# espnative-deadrail-2-c.net
KiCad netlist of a schematic drawn in EAGLE
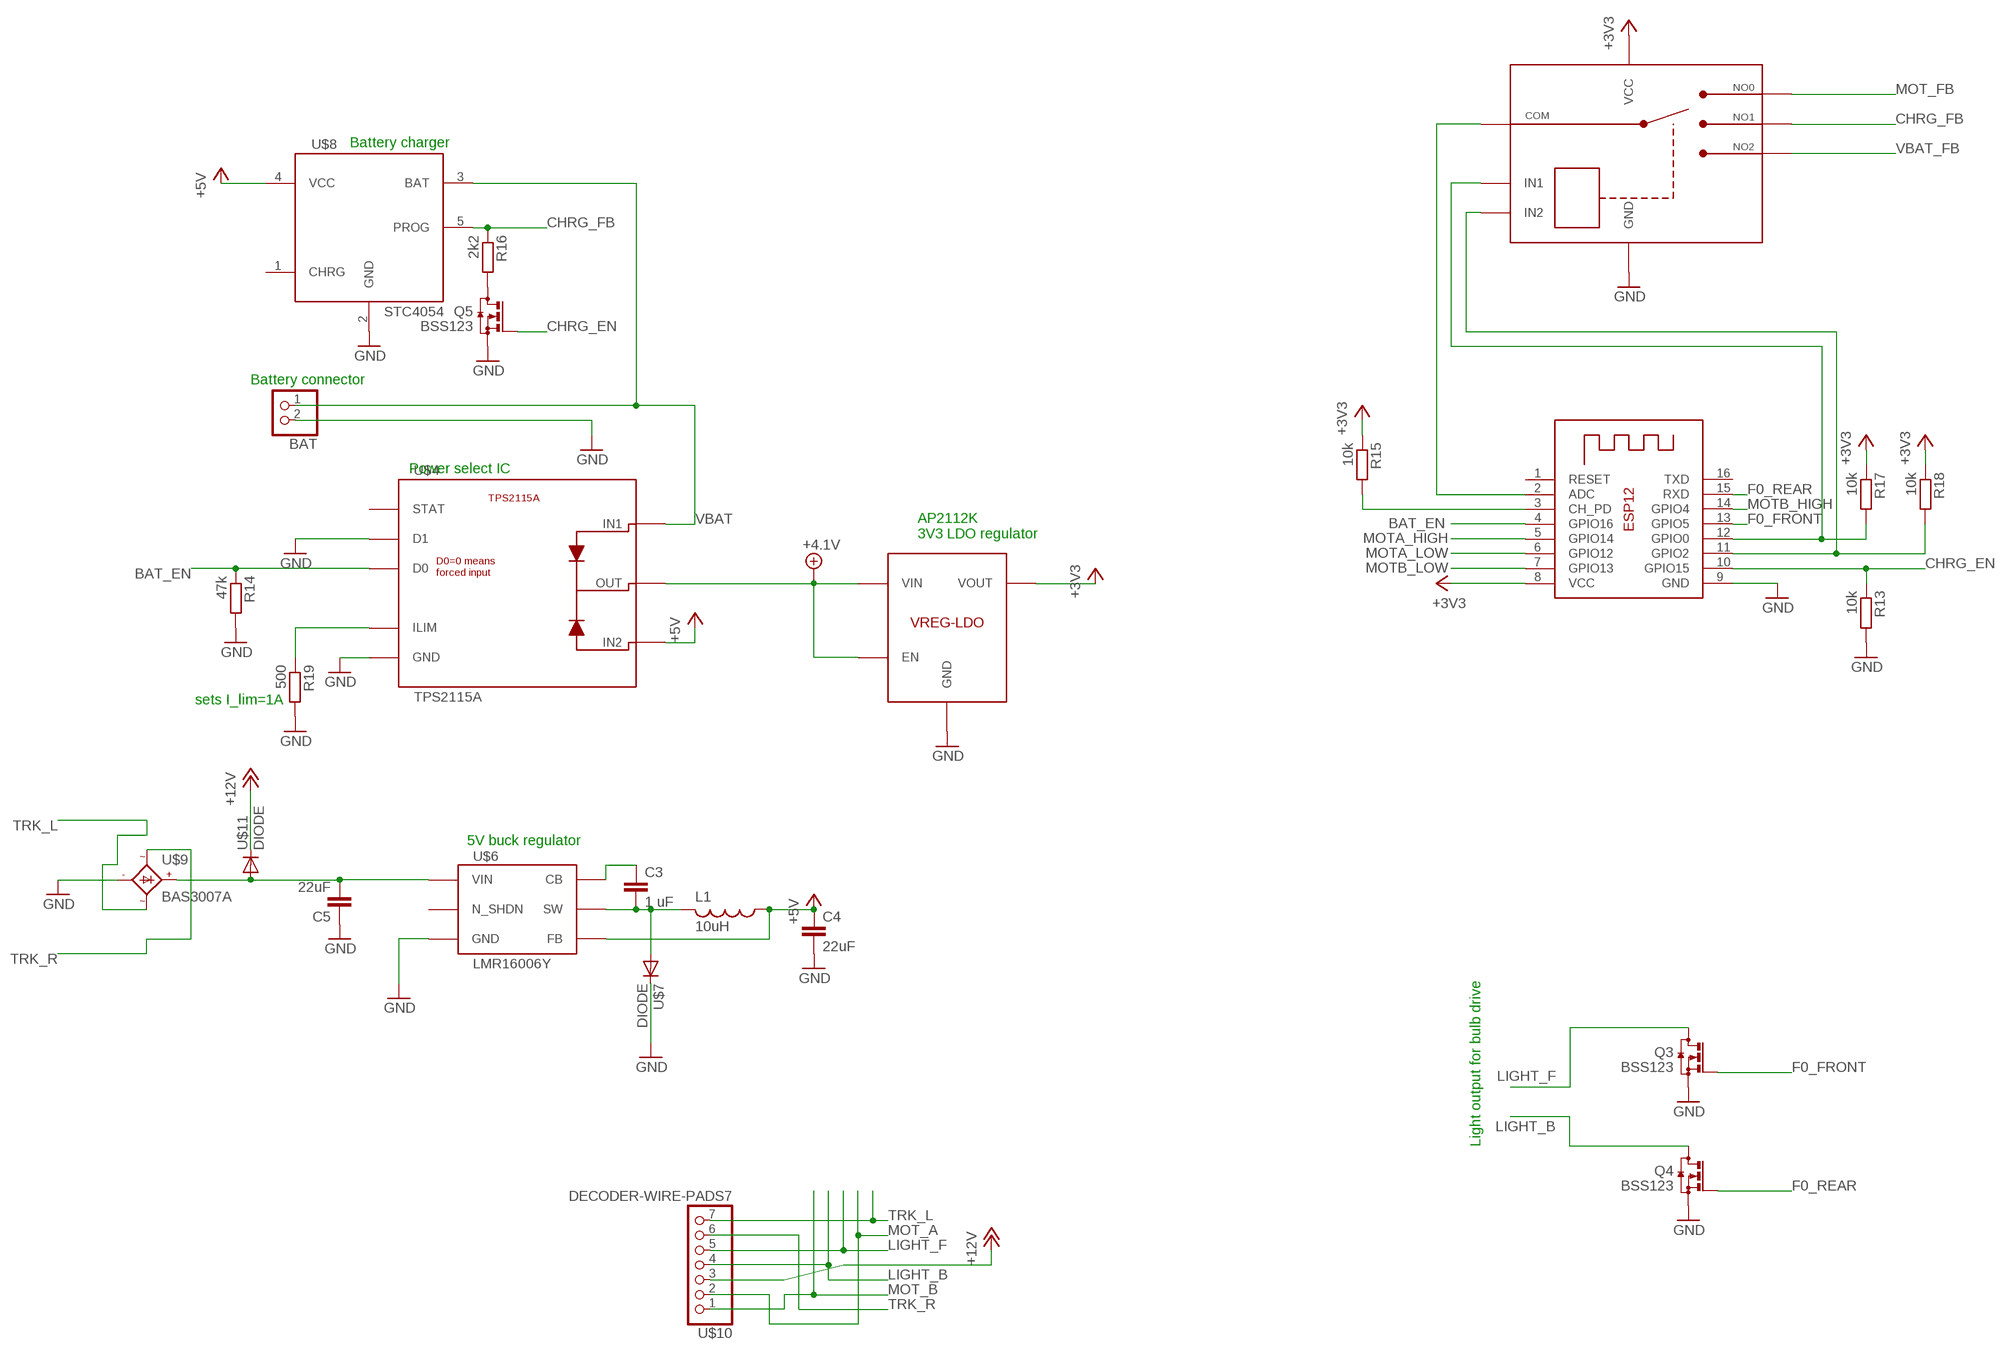
[diagram p0: schematic, sheet 1, part 1 of 2]
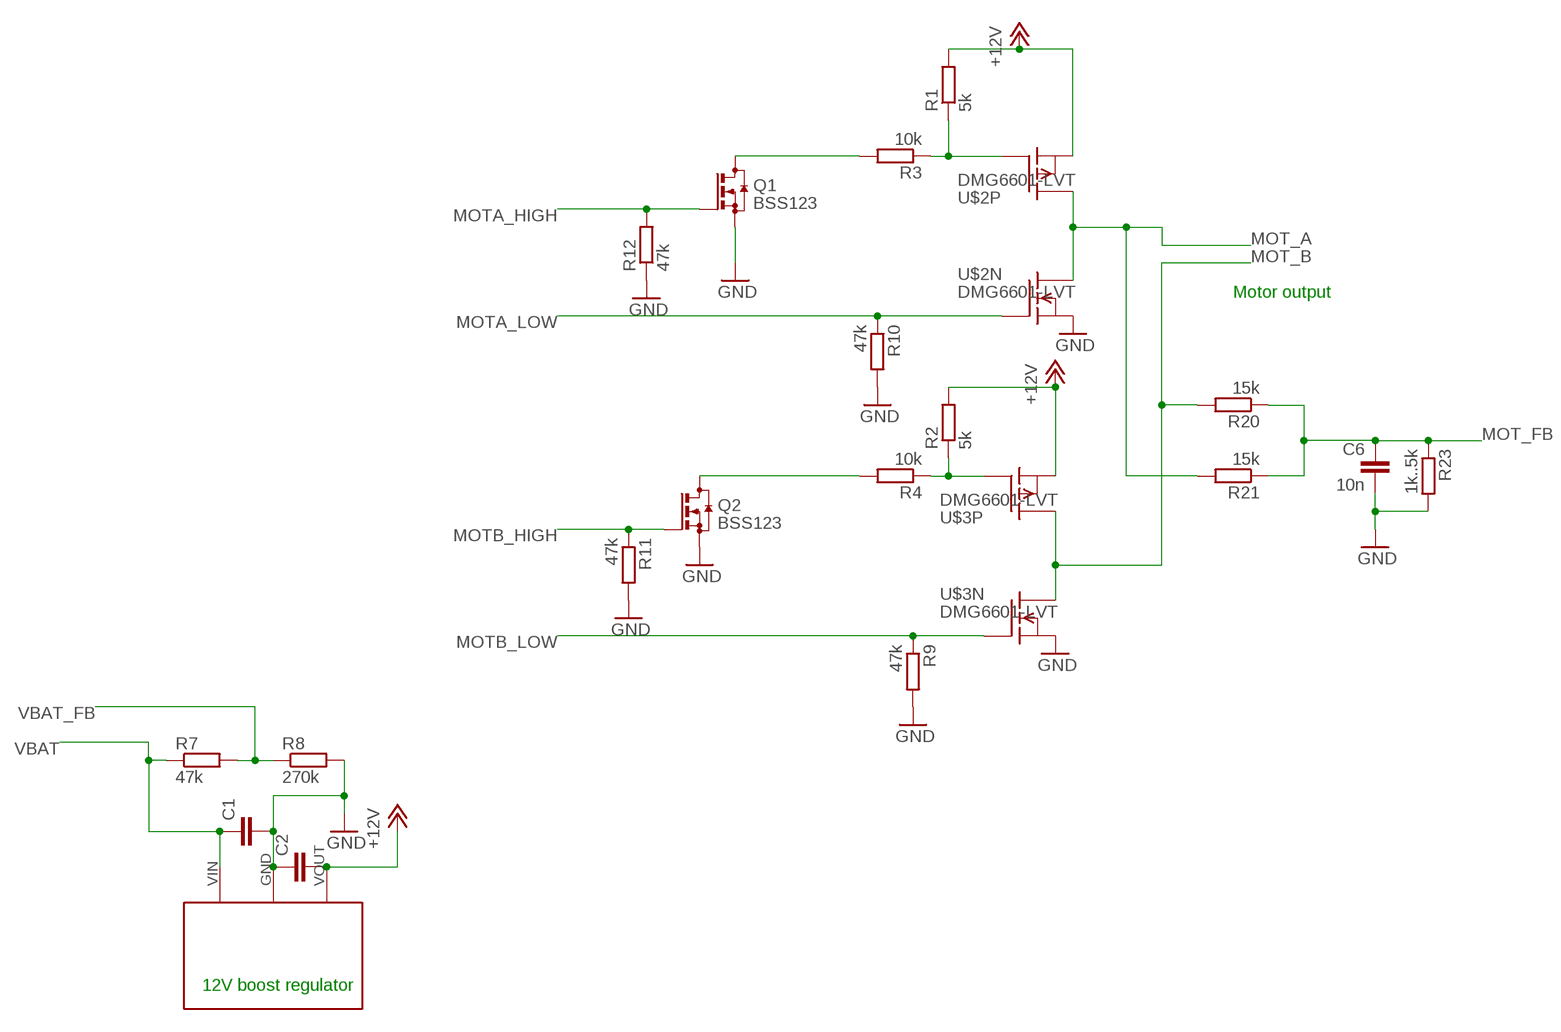
[diagram p1: schematic, sheet 1, part 2 of 2]

(export (version "E")
  (design (tool "Eeschema 10.0.6"))
  (components
    (comp (ref "BAT")
      (value "JST_2PIN-SMT-RA")
      (footprint "eagle-import:JST-PH-2-SMT-RA")
      (libsource (lib "eagle-import") (part "JST_2PIN-SMT-RA"))
    )
    (comp (ref "C1")
      (value "C-EUC1206")
      (footprint "eagle-import:C1206")
      (libsource (lib "eagle-import") (part "C-EUC1206"))
    )
    (comp (ref "C2")
      (value "C-EUC1206")
      (footprint "eagle-import:C1206")
      (libsource (lib "eagle-import") (part "C-EUC1206"))
    )
    (comp (ref "C3")
      (value "1 uF")
      (footprint "eagle-import:C0603")
      (libsource (lib "eagle-import") (part "C-EUC0603"))
    )
    (comp (ref "C4")
      (value "22uF")
      (footprint "eagle-import:C0603")
      (libsource (lib "eagle-import") (part "C-EUC0603"))
    )
    (comp (ref "C5")
      (value "22uF")
      (footprint "eagle-import:C1206")
      (libsource (lib "eagle-import") (part "C-EUC1206"))
    )
    (comp (ref "C6")
      (value "10n")
      (footprint "eagle-import:C0603")
      (libsource (lib "eagle-import") (part "C-EUC0603"))
    )
    (comp (ref "L1")
      (value "10uH")
      (footprint "eagle-import:FDSD0420")
      (libsource (lib "eagle-import") (part "FDSD0420"))
    )
    (comp (ref "Q1")
      (value "BSS123")
      (footprint "eagle-import:SOT23")
      (libsource (lib "eagle-import") (part "BSS123"))
    )
    (comp (ref "Q2")
      (value "BSS123")
      (footprint "eagle-import:SOT23")
      (libsource (lib "eagle-import") (part "BSS123"))
    )
    (comp (ref "Q3")
      (value "BSS123")
      (footprint "eagle-import:SOT23")
      (libsource (lib "eagle-import") (part "BSS123"))
    )
    (comp (ref "Q4")
      (value "BSS123")
      (footprint "eagle-import:SOT23")
      (libsource (lib "eagle-import") (part "BSS123"))
    )
    (comp (ref "Q5")
      (value "BSS123")
      (footprint "eagle-import:SOT23")
      (libsource (lib "eagle-import") (part "BSS123"))
    )
    (comp (ref "R1")
      (value "5k")
      (footprint "eagle-import:R0603")
      (libsource (lib "eagle-import") (part "R-EU_R0603"))
    )
    (comp (ref "R2")
      (value "5k")
      (footprint "eagle-import:R0603")
      (libsource (lib "eagle-import") (part "R-EU_R0603"))
    )
    (comp (ref "R3")
      (value "10k")
      (footprint "eagle-import:R0603")
      (libsource (lib "eagle-import") (part "R-EU_R0603"))
    )
    (comp (ref "R4")
      (value "10k")
      (footprint "eagle-import:R0603")
      (libsource (lib "eagle-import") (part "R-EU_R0603"))
    )
    (comp (ref "R7")
      (value "47k")
      (footprint "eagle-import:R0603")
      (libsource (lib "eagle-import") (part "R-EU_R0603"))
    )
    (comp (ref "R8")
      (value "270k")
      (footprint "eagle-import:R0603")
      (libsource (lib "eagle-import") (part "R-EU_R0603"))
    )
    (comp (ref "R9")
      (value "47k")
      (footprint "eagle-import:R0603")
      (libsource (lib "eagle-import") (part "R-EU_R0603"))
    )
    (comp (ref "R10")
      (value "47k")
      (footprint "eagle-import:R0603")
      (libsource (lib "eagle-import") (part "R-EU_R0603"))
    )
    (comp (ref "R11")
      (value "47k")
      (footprint "eagle-import:R0603")
      (libsource (lib "eagle-import") (part "R-EU_R0603"))
    )
    (comp (ref "R12")
      (value "47k")
      (footprint "eagle-import:R0603")
      (libsource (lib "eagle-import") (part "R-EU_R0603"))
    )
    (comp (ref "R13")
      (value "10k")
      (footprint "eagle-import:R0603")
      (libsource (lib "eagle-import") (part "R-EU_R0603"))
    )
    (comp (ref "R14")
      (value "47k")
      (footprint "eagle-import:R0603")
      (libsource (lib "eagle-import") (part "R-EU_R0603"))
    )
    (comp (ref "R15")
      (value "10k")
      (footprint "eagle-import:R0603")
      (libsource (lib "eagle-import") (part "R-EU_R0603"))
    )
    (comp (ref "R16")
      (value "2k2")
      (footprint "eagle-import:R0603")
      (libsource (lib "eagle-import") (part "R-EU_R0603"))
    )
    (comp (ref "R17")
      (value "10k")
      (footprint "eagle-import:R0603")
      (libsource (lib "eagle-import") (part "R-EU_R0603"))
    )
    (comp (ref "R18")
      (value "10k")
      (footprint "eagle-import:R0603")
      (libsource (lib "eagle-import") (part "R-EU_R0603"))
    )
    (comp (ref "R19")
      (value "500")
      (footprint "eagle-import:R0603")
      (libsource (lib "eagle-import") (part "R-EU_R0603"))
    )
    (comp (ref "R20")
      (value "15k")
      (footprint "eagle-import:R0603")
      (libsource (lib "eagle-import") (part "R-EU_R0603"))
    )
    (comp (ref "R21")
      (value "15k")
      (footprint "eagle-import:R0603")
      (libsource (lib "eagle-import") (part "R-EU_R0603"))
    )
    (comp (ref "R23")
      (value "1k..5k")
      (footprint "eagle-import:R0603")
      (libsource (lib "eagle-import") (part "R-EU_R0603"))
    )
    (comp (ref "U$1")
      (value "AP2112K-3V3")
      (footprint "eagle-import:SOT23-5L")
      (libsource (lib "eagle-import") (part "AP2112K"))
    )
    (comp (ref "U$2")
      (value "DMG6601-LVT")
      (footprint "eagle-import:TSOT-26")
      (libsource (lib "eagle-import") (part "DMG6601-LVT"))
    )
    (comp (ref "U$3")
      (value "DMG6601-LVT")
      (footprint "eagle-import:TSOT-26")
      (libsource (lib "eagle-import") (part "DMG6601-LVT"))
    )
    (comp (ref "U$4")
      (value "TPS2115A")
      (footprint "eagle-import:TSSOP-8")
      (libsource (lib "eagle-import") (part "TPS2115A"))
    )
    (comp (ref "U$5")
      (value "POLOLU-VREG12")
      (footprint "eagle-import:POLOLU-REGULATOR")
      (libsource (lib "eagle-import") (part "POLOLU-VREG12"))
    )
    (comp (ref "U$6")
      (value "LMR16006Y")
      (footprint "eagle-import:SOT23-6")
      (libsource (lib "eagle-import") (part "LMR16006Y"))
    )
    (comp (ref "U$7")
      (value "DIODE")
      (footprint "eagle-import:DIODE-1206")
      (libsource (lib "eagle-import") (part "DIODE"))
    )
    (comp (ref "U$8")
      (value "STC4054")
      (footprint "eagle-import:SOT23-5L")
      (libsource (lib "eagle-import") (part "STC4054"))
    )
    (comp (ref "U$9")
      (value "BAS3007A")
      (footprint "eagle-import:SOT143B")
      (libsource (lib "eagle-import") (part "BAS3007A"))
    )
    (comp (ref "U$10")
      (value "DECODER-WIRE-PADS7")
      (footprint "eagle-import:DECODER-WIRE-PADS")
      (libsource (lib "eagle-import") (part "DECODER-WIRE-PADS7"))
    )
    (comp (ref "U$11")
      (value "DIODE")
      (footprint "eagle-import:DIODE-1206")
      (libsource (lib "eagle-import") (part "DIODE"))
    )
    (comp (ref "U$12")
      (value "TS5A3359")
      (footprint "eagle-import:US8")
      (libsource (lib "eagle-import") (part "TS5A3359"))
    )
    (comp (ref "X1")
      (value "ESP-12")
      (footprint "eagle-import:ESP-12")
      (libsource (lib "eagle-import") (part "ESP-12"))
    )
  )
  (nets
    (net (code "1") (name "+3V3") (class "Default")
      (node (ref "R15") (pin "1") (pinfunction "1_1") (pintype "passive"))
      (node (ref "R17") (pin "1") (pinfunction "1_1") (pintype "passive"))
      (node (ref "R18") (pin "1") (pinfunction "1_1") (pintype "passive"))
      (node (ref "U$1") (pin "5") (pinfunction "VOUT_5") (pintype "bidirectional"))
      (node (ref "U$12") (pin "8") (pinfunction "VCC_8") (pintype "bidirectional"))
      (node (ref "X1") (pin "8") (pinfunction "VCC_8") (pintype "power_in"))
    )
    (net (code "2") (name "+4.1V") (class "Default")
      (node (ref "U$1") (pin "1") (pinfunction "VIN_1") (pintype "bidirectional"))
      (node (ref "U$1") (pin "3") (pinfunction "EN_3") (pintype "bidirectional"))
      (node (ref "U$4") (pin "7") (pinfunction "OUT_7") (pintype "bidirectional"))
    )
    (net (code "3") (name "+5V") (class "Default")
      (node (ref "C4") (pin "1") (pinfunction "1_1") (pintype "passive"))
      (node (ref "L1") (pin "P$1") (pinfunction "1_P$1") (pintype "passive"))
      (node (ref "U$4") (pin "6") (pinfunction "IN2_6") (pintype "bidirectional"))
      (node (ref "U$6") (pin "3") (pinfunction "FB_3") (pintype "bidirectional"))
      (node (ref "U$8") (pin "4") (pinfunction "VCC_4") (pintype "bidirectional"))
    )
    (net (code "4") (name "+12V") (class "Default")
      (node (ref "C2") (pin "2") (pinfunction "2_2") (pintype "passive"))
      (node (ref "R1") (pin "2") (pinfunction "2_2") (pintype "passive"))
      (node (ref "R2") (pin "2") (pinfunction "2_2") (pintype "passive"))
      (node (ref "U$10") (pin "3") (pinfunction "3_3") (pintype "passive"))
      (node (ref "U$11") (pin "C") (pinfunction "C_C") (pintype "passive"))
      (node (ref "U$2") (pin "2") (pinfunction "S_2") (pintype "passive"))
      (node (ref "U$3") (pin "2") (pinfunction "S_2") (pintype "passive"))
      (node (ref "U$5") (pin "VOUT") (pinfunction "VOUT_VOUT") (pintype "bidirectional"))
    )
    (net (code "5") (name "/BAT_EN") (class "Default")
      (node (ref "R14") (pin "1") (pinfunction "1_1") (pintype "passive"))
      (node (ref "U$4") (pin "2") (pinfunction "D0_2") (pintype "bidirectional"))
      (node (ref "X1") (pin "4") (pinfunction "GPIO16_4") (pintype "bidirectional"))
    )
    (net (code "6") (name "/CHRG_EN") (class "Default")
      (node (ref "Q5") (pin "1") (pinfunction "G_1") (pintype "passive"))
      (node (ref "R13") (pin "1") (pinfunction "1_1") (pintype "passive"))
      (node (ref "X1") (pin "10") (pinfunction "GPIO15_10") (pintype "bidirectional"))
    )
    (net (code "7") (name "/CHRG_FB") (class "Default")
      (node (ref "R16") (pin "1") (pinfunction "1_1") (pintype "passive"))
      (node (ref "U$12") (pin "2") (pinfunction "NO1_2") (pintype "bidirectional"))
      (node (ref "U$8") (pin "5") (pinfunction "PROG_5") (pintype "bidirectional"))
    )
    (net (code "8") (name "/F0_FRONT") (class "Default")
      (node (ref "Q3") (pin "1") (pinfunction "G_1") (pintype "passive"))
      (node (ref "X1") (pin "13") (pinfunction "GPIO5_13") (pintype "bidirectional"))
    )
    (net (code "9") (name "/F0_REAR") (class "Default")
      (node (ref "Q4") (pin "1") (pinfunction "G_1") (pintype "passive"))
      (node (ref "X1") (pin "15") (pinfunction "RXD_15") (pintype "input"))
    )
    (net (code "10") (name "/LIGHT_B") (class "Default")
      (node (ref "Q4") (pin "3") (pinfunction "D_3") (pintype "passive"))
      (node (ref "U$10") (pin "4") (pinfunction "4_4") (pintype "passive"))
    )
    (net (code "11") (name "/LIGHT_F") (class "Default")
      (node (ref "Q3") (pin "3") (pinfunction "D_3") (pintype "passive"))
      (node (ref "U$10") (pin "5") (pinfunction "5_5") (pintype "passive"))
    )
    (net (code "12") (name "/MOTA_HIGH") (class "Default")
      (node (ref "Q1") (pin "1") (pinfunction "G_1") (pintype "passive"))
      (node (ref "R12") (pin "2") (pinfunction "2_2") (pintype "passive"))
      (node (ref "X1") (pin "5") (pinfunction "GPIO14_5") (pintype "bidirectional"))
    )
    (net (code "13") (name "/MOTA_LOW") (class "Default")
      (node (ref "R10") (pin "1") (pinfunction "1_1") (pintype "passive"))
      (node (ref "U$2") (pin "1") (pinfunction "G_1") (pintype "passive"))
      (node (ref "X1") (pin "6") (pinfunction "GPIO12_6") (pintype "bidirectional"))
    )
    (net (code "14") (name "/MOTB_HIGH") (class "Default")
      (node (ref "Q2") (pin "1") (pinfunction "G_1") (pintype "passive"))
      (node (ref "R11") (pin "1") (pinfunction "1_1") (pintype "passive"))
      (node (ref "X1") (pin "14") (pinfunction "GPIO4_14") (pintype "bidirectional"))
    )
    (net (code "15") (name "/MOTB_LOW") (class "Default")
      (node (ref "R9") (pin "1") (pinfunction "1_1") (pintype "passive"))
      (node (ref "U$3") (pin "1") (pinfunction "G_1") (pintype "passive"))
      (node (ref "X1") (pin "7") (pinfunction "GPIO13_7") (pintype "bidirectional"))
    )
    (net (code "16") (name "/MOT_A") (class "Default")
      (node (ref "R21") (pin "2") (pinfunction "2_2") (pintype "passive"))
      (node (ref "U$10") (pin "2") (pinfunction "2_2") (pintype "passive"))
      (node (ref "U$2") (pin "4") (pinfunction "D_4") (pintype "passive"))
      (node (ref "U$2") (pin "6") (pinfunction "D_6") (pintype "passive"))
    )
    (net (code "17") (name "/MOT_B") (class "Default")
      (node (ref "R20") (pin "2") (pinfunction "2_2") (pintype "passive"))
      (node (ref "U$10") (pin "1") (pinfunction "1_1") (pintype "passive"))
      (node (ref "U$3") (pin "4") (pinfunction "D_4") (pintype "passive"))
      (node (ref "U$3") (pin "6") (pinfunction "D_6") (pintype "passive"))
    )
    (net (code "18") (name "/MOT_FB") (class "Default")
      (node (ref "C6") (pin "1") (pinfunction "1_1") (pintype "passive"))
      (node (ref "R20") (pin "1") (pinfunction "1_1") (pintype "passive"))
      (node (ref "R21") (pin "1") (pinfunction "1_1") (pintype "passive"))
      (node (ref "R23") (pin "1") (pinfunction "1_1") (pintype "passive"))
      (node (ref "U$12") (pin "1") (pinfunction "NO0_1") (pintype "bidirectional"))
    )
    (net (code "19") (name "/TRK_L") (class "Default")
      (node (ref "U$10") (pin "7") (pinfunction "7_7") (pintype "passive"))
      (node (ref "U$9") (pin "3") (pinfunction "AC2_3") (pintype "passive"))
    )
    (net (code "20") (name "/TRK_R") (class "Default")
      (node (ref "U$10") (pin "6") (pinfunction "6_6") (pintype "passive"))
      (node (ref "U$9") (pin "2") (pinfunction "AC1_2") (pintype "passive"))
    )
    (net (code "21") (name "/VBAT") (class "Default")
      (node (ref "BAT") (pin "1") (pinfunction "2_1") (pintype "passive"))
      (node (ref "C1") (pin "1") (pinfunction "1_1") (pintype "passive"))
      (node (ref "R7") (pin "1") (pinfunction "1_1") (pintype "passive"))
      (node (ref "U$4") (pin "8") (pinfunction "IN1_8") (pintype "bidirectional"))
      (node (ref "U$5") (pin "VIN") (pinfunction "VIN_VIN") (pintype "bidirectional"))
      (node (ref "U$8") (pin "3") (pinfunction "BAT_3") (pintype "bidirectional"))
    )
    (net (code "22") (name "/VBAT_FB") (class "Default")
      (node (ref "R7") (pin "2") (pinfunction "2_2") (pintype "passive"))
      (node (ref "R8") (pin "1") (pinfunction "1_1") (pintype "passive"))
      (node (ref "U$12") (pin "3") (pinfunction "NO2_3") (pintype "bidirectional"))
    )
    (net (code "23") (name "GND") (class "Default")
      (node (ref "BAT") (pin "2") (pinfunction "1_2") (pintype "passive"))
      (node (ref "C1") (pin "2") (pinfunction "2_2") (pintype "passive"))
      (node (ref "C2") (pin "1") (pinfunction "1_1") (pintype "passive"))
      (node (ref "C4") (pin "2") (pinfunction "2_2") (pintype "passive"))
      (node (ref "C5") (pin "1") (pinfunction "1_1") (pintype "passive"))
      (node (ref "C6") (pin "2") (pinfunction "2_2") (pintype "passive"))
      (node (ref "Q1") (pin "2") (pinfunction "S_2") (pintype "passive"))
      (node (ref "Q2") (pin "2") (pinfunction "S_2") (pintype "passive"))
      (node (ref "Q3") (pin "2") (pinfunction "S_2") (pintype "passive"))
      (node (ref "Q4") (pin "2") (pinfunction "S_2") (pintype "passive"))
      (node (ref "Q5") (pin "2") (pinfunction "S_2") (pintype "passive"))
      (node (ref "R10") (pin "2") (pinfunction "2_2") (pintype "passive"))
      (node (ref "R11") (pin "2") (pinfunction "2_2") (pintype "passive"))
      (node (ref "R12") (pin "1") (pinfunction "1_1") (pintype "passive"))
      (node (ref "R13") (pin "2") (pinfunction "2_2") (pintype "passive"))
      (node (ref "R14") (pin "2") (pinfunction "2_2") (pintype "passive"))
      (node (ref "R19") (pin "2") (pinfunction "2_2") (pintype "passive"))
      (node (ref "R23") (pin "2") (pinfunction "2_2") (pintype "passive"))
      (node (ref "R8") (pin "2") (pinfunction "2_2") (pintype "passive"))
      (node (ref "R9") (pin "2") (pinfunction "2_2") (pintype "passive"))
      (node (ref "U$1") (pin "2") (pinfunction "GND_2") (pintype "bidirectional"))
      (node (ref "U$12") (pin "4") (pinfunction "GND_4") (pintype "bidirectional"))
      (node (ref "U$2") (pin "5") (pinfunction "S_5") (pintype "passive"))
      (node (ref "U$3") (pin "5") (pinfunction "S_5") (pintype "passive"))
      (node (ref "U$4") (pin "3") (pinfunction "D1_3") (pintype "bidirectional"))
      (node (ref "U$4") (pin "5") (pinfunction "GND_5") (pintype "bidirectional"))
      (node (ref "U$5") (pin "GND") (pinfunction "GND_GND") (pintype "bidirectional"))
      (node (ref "U$6") (pin "2") (pinfunction "GND_2") (pintype "bidirectional"))
      (node (ref "U$7") (pin "C") (pinfunction "C_C") (pintype "passive"))
      (node (ref "U$8") (pin "2") (pinfunction "GND_2") (pintype "bidirectional"))
      (node (ref "U$9") (pin "1") (pinfunction "-_1") (pintype "passive"))
      (node (ref "X1") (pin "9") (pinfunction "GND_9") (pintype "power_in"))
    )
    (net (code "24") (name "Net-(L1-2)") (class "Default")
      (node (ref "C3") (pin "2") (pinfunction "2_2") (pintype "passive"))
      (node (ref "L1") (pin "P$2") (pinfunction "2_P$2") (pintype "passive"))
      (node (ref "U$6") (pin "6") (pinfunction "SW_6") (pintype "bidirectional"))
      (node (ref "U$7") (pin "A") (pinfunction "A_A") (pintype "passive"))
    )
    (net (code "25") (name "Net-(Q1-D)") (class "Default")
      (node (ref "Q1") (pin "3") (pinfunction "D_3") (pintype "passive"))
      (node (ref "R3") (pin "2") (pinfunction "2_2") (pintype "passive"))
    )
    (net (code "26") (name "Net-(Q2-D)") (class "Default")
      (node (ref "Q2") (pin "3") (pinfunction "D_3") (pintype "passive"))
      (node (ref "R4") (pin "2") (pinfunction "2_2") (pintype "passive"))
    )
    (net (code "27") (name "Net-(Q5-D)") (class "Default")
      (node (ref "Q5") (pin "3") (pinfunction "D_3") (pintype "passive"))
      (node (ref "R16") (pin "2") (pinfunction "2_2") (pintype "passive"))
    )
    (net (code "28") (name "Net-(U$2B-G)") (class "Default")
      (node (ref "R1") (pin "1") (pinfunction "1_1") (pintype "passive"))
      (node (ref "R3") (pin "1") (pinfunction "1_1") (pintype "passive"))
      (node (ref "U$2") (pin "3") (pinfunction "G_3") (pintype "passive"))
    )
    (net (code "29") (name "Net-(U$3B-G)") (class "Default")
      (node (ref "R2") (pin "1") (pinfunction "1_1") (pintype "passive"))
      (node (ref "R4") (pin "1") (pinfunction "1_1") (pintype "passive"))
      (node (ref "U$3") (pin "3") (pinfunction "G_3") (pintype "passive"))
    )
    (net (code "30") (name "Net-(U$4-ILIM)") (class "Default")
      (node (ref "R19") (pin "1") (pinfunction "1_1") (pintype "passive"))
      (node (ref "U$4") (pin "4") (pinfunction "ILIM_4") (pintype "bidirectional"))
    )
    (net (code "31") (name "Net-(U$6-CB)") (class "Default")
      (node (ref "C3") (pin "1") (pinfunction "1_1") (pintype "passive"))
      (node (ref "U$6") (pin "1") (pinfunction "CB_1") (pintype "bidirectional"))
    )
    (net (code "32") (name "Net-(U$6-VIN)") (class "Default")
      (node (ref "C5") (pin "2") (pinfunction "2_2") (pintype "passive"))
      (node (ref "U$11") (pin "A") (pinfunction "A_A") (pintype "passive"))
      (node (ref "U$6") (pin "5") (pinfunction "VIN_5") (pintype "bidirectional"))
      (node (ref "U$9") (pin "4") (pinfunction "+_4") (pintype "passive"))
    )
    (net (code "33") (name "Net-(U$12-COM)") (class "Default")
      (node (ref "U$12") (pin "7") (pinfunction "COM_7") (pintype "bidirectional"))
      (node (ref "X1") (pin "2") (pinfunction "ADC_2") (pintype "passive"))
    )
    (net (code "34") (name "Net-(U$12-IN1)") (class "Default")
      (node (ref "R17") (pin "2") (pinfunction "2_2") (pintype "passive"))
      (node (ref "U$12") (pin "6") (pinfunction "IN1_6") (pintype "bidirectional"))
      (node (ref "X1") (pin "12") (pinfunction "GPIO0_12") (pintype "bidirectional"))
    )
    (net (code "35") (name "Net-(U$12-IN2)") (class "Default")
      (node (ref "R18") (pin "2") (pinfunction "2_2") (pintype "passive"))
      (node (ref "U$12") (pin "5") (pinfunction "IN2_5") (pintype "bidirectional"))
      (node (ref "X1") (pin "11") (pinfunction "GPIO2_11") (pintype "bidirectional"))
    )
    (net (code "36") (name "Net-(X1-CH_PD)") (class "Default")
      (node (ref "R15") (pin "2") (pinfunction "2_2") (pintype "passive"))
      (node (ref "X1") (pin "3") (pinfunction "CH_PD_3") (pintype "input"))
    )
    (net (code "37") (name "unconnected-(U$4-STAT-Pad1)") (class "Default")
      (node (ref "U$4") (pin "1") (pinfunction "STAT_1") (pintype "bidirectional"))
    )
    (net (code "38") (name "unconnected-(U$6-N_SHDN-Pad4)") (class "Default")
      (node (ref "U$6") (pin "4") (pinfunction "N_SHDN_4") (pintype "bidirectional"))
    )
    (net (code "39") (name "unconnected-(U$8-CHRG-Pad1)") (class "Default")
      (node (ref "U$8") (pin "1") (pinfunction "CHRG_1") (pintype "bidirectional"))
    )
    (net (code "40") (name "unconnected-(X1-RESET-Pad1)") (class "Default")
      (node (ref "X1") (pin "1") (pinfunction "RESET_1") (pintype "input"))
    )
    (net (code "41") (name "unconnected-(X1-TXD-Pad16)") (class "Default")
      (node (ref "X1") (pin "16") (pinfunction "TXD_16") (pintype "output"))
    )
  )
)
